# PowerSupply.net
KiCad netlist of a schematic drawn in Altium Designer
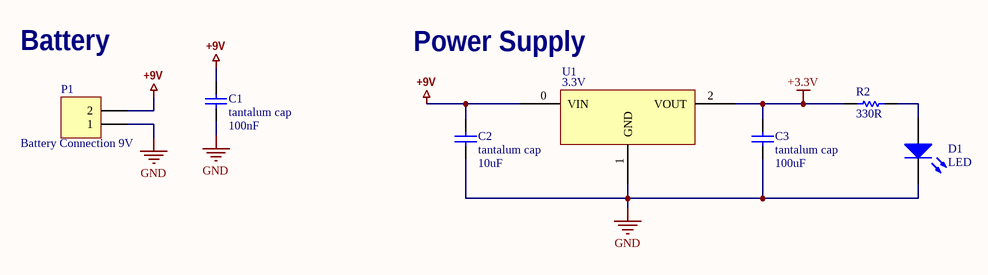
[diagram p0: PowerSupply.SchDoc]

(export (version "E")
  (design (tool "Eeschema 10.0.6"))
  (components
    (comp (ref "C1")
      (value "tantalum cap")
      (footprint "C1206tancap")
      (description "Capacitor (Semiconductor SIM Model)")
      (fields (field (name "ALTIUM_VALUE") "100nF") (field (name "PUBLISHER") "Altium Limited"))
      (libsource (lib "smartmcu") (part "Cap Semi_6"))
    )
    (comp (ref "C2")
      (value "tantalum cap")
      (footprint "C1206tancap")
      (description "Capacitor (Semiconductor SIM Model)")
      (fields (field (name "ALTIUM_VALUE") "10uF") (field (name "PUBLISHER") "Altium Limited"))
      (libsource (lib "smartmcu") (part "Cap Semi_5"))
    )
    (comp (ref "C3")
      (value "tantalum cap")
      (footprint "C1206tancap")
      (description "Capacitor (Semiconductor SIM Model)")
      (fields (field (name "ALTIUM_VALUE") "100uF") (field (name "PUBLISHER") "Altium Limited"))
      (libsource (lib "smartmcu") (part "Cap Semi_6"))
    )
    (comp (ref "D1")
      (value "LED")
      (footprint "MY_LED_0805")
      (description "Typical INFRARED GaAs LED")
      (fields (field (name "ASID PART NUMBER") "LED-AS"))
      (libsource (lib "Mylib+Rev+4") (part "LED"))
    )
    (comp (ref "P1")
      (value "Battery Connection 9V")
      (footprint "HDR1X2H3dbody")
      (description "Header, 2-Pin, Right Angle")
      (fields (field (name "VOLTAGE") "9V") (field (name "PUBLISHER") "Altium Limited"))
      (libsource (lib "smartmcu") (part "Header 2H"))
    )
    (comp (ref "R2")
      (value "330R")
      (footprint "MY_0805")
      (description "Standard resistor")
      (fields (field (name "ASID PART NUMBER") "Res-AS"))
      (libsource (lib "Mylib+Rev+4") (part "Res"))
    )
    (comp (ref "U1")
      (value "~")
      (footprint "4-Pin SOT")
      (fields (field (name "OUTPUT VOLTAGE") "3.3V"))
      (libsource (lib "Smart_MCU") (part "lm1117"))
    )
  )
  (nets
    (net (code "1") (name "+3.3V") (class "Default")
      (node (ref "C3") (pin "2") (pinfunction "2_2") (pintype "passive"))
      (node (ref "R2") (pin "1") (pinfunction "1_1") (pintype "passive"))
      (node (ref "U1") (pin "2") (pinfunction "VOUT_2") (pintype "passive"))
    )
    (net (code "2") (name "+9V") (class "Default")
      (node (ref "C1") (pin "2") (pinfunction "2_2") (pintype "passive"))
      (node (ref "C2") (pin "2") (pinfunction "2_2") (pintype "passive"))
      (node (ref "P1") (pin "2") (pinfunction "2_2") (pintype "passive"))
      (node (ref "U1") (pin "0") (pinfunction "VIN_0") (pintype "passive"))
    )
    (net (code "3") (name "GND") (class "Default")
      (node (ref "C1") (pin "1") (pinfunction "1_1") (pintype "passive"))
      (node (ref "C2") (pin "1") (pinfunction "1_1") (pintype "passive"))
      (node (ref "C3") (pin "1") (pinfunction "1_1") (pintype "passive"))
      (node (ref "D1") (pin "K") (pinfunction "K_K") (pintype "passive"))
      (node (ref "P1") (pin "1") (pinfunction "1_1") (pintype "passive"))
      (node (ref "U1") (pin "1") (pinfunction "GND_1") (pintype "passive"))
    )
    (net (code "4") (name "Net-(D1-PadA)") (class "Default")
      (node (ref "D1") (pin "A") (pinfunction "A_A") (pintype "passive"))
      (node (ref "R2") (pin "2") (pinfunction "2_2") (pintype "passive"))
    )
  )
)
